# PI-Shield.net
KiCad netlist of a schematic drawn in EAGLE
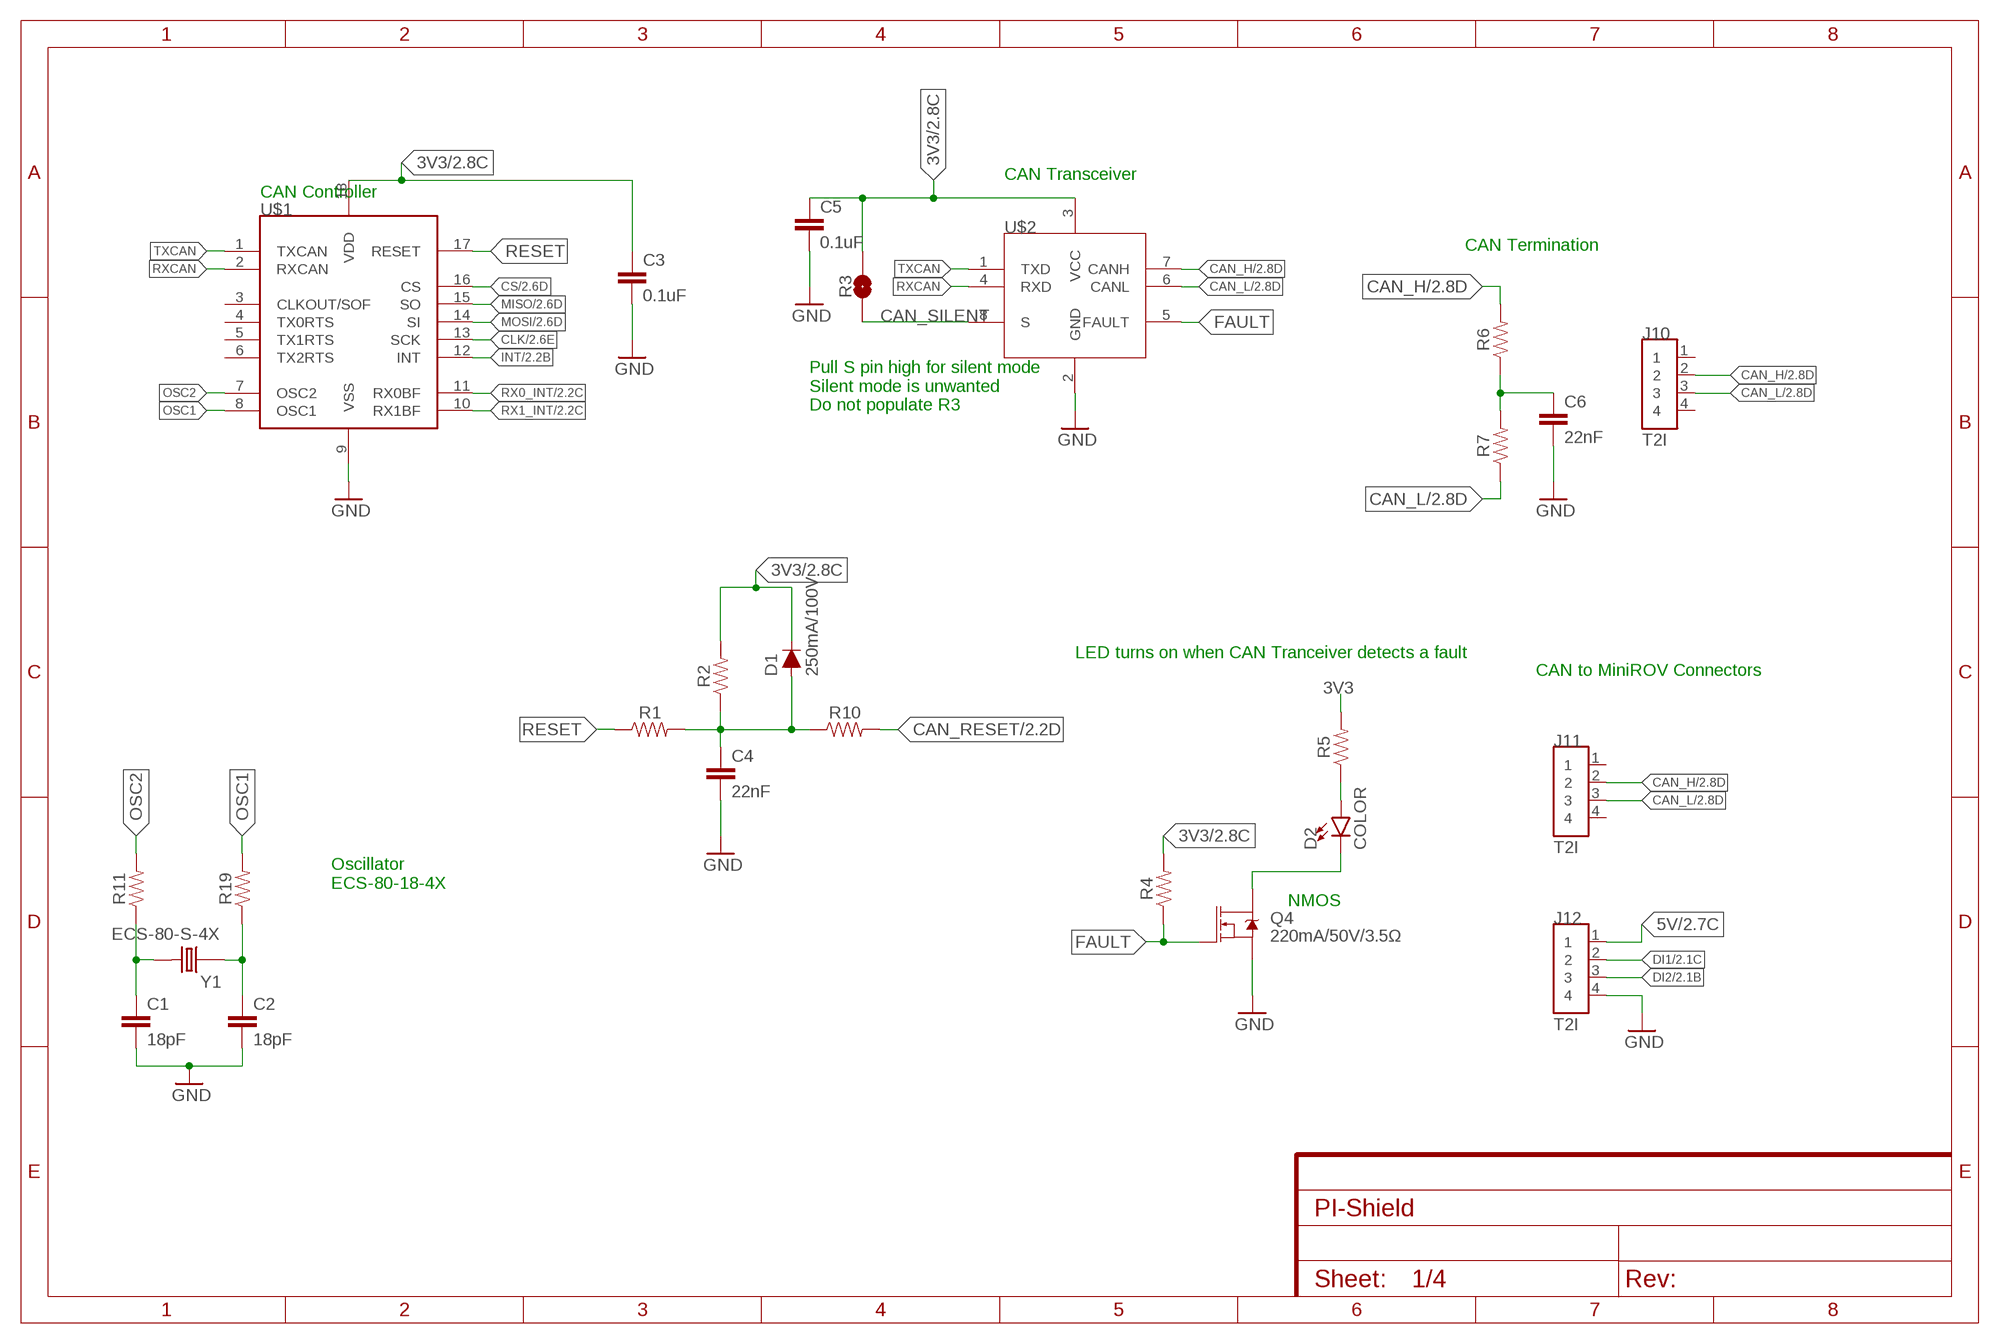
[diagram p0: schematic, sheet 1]
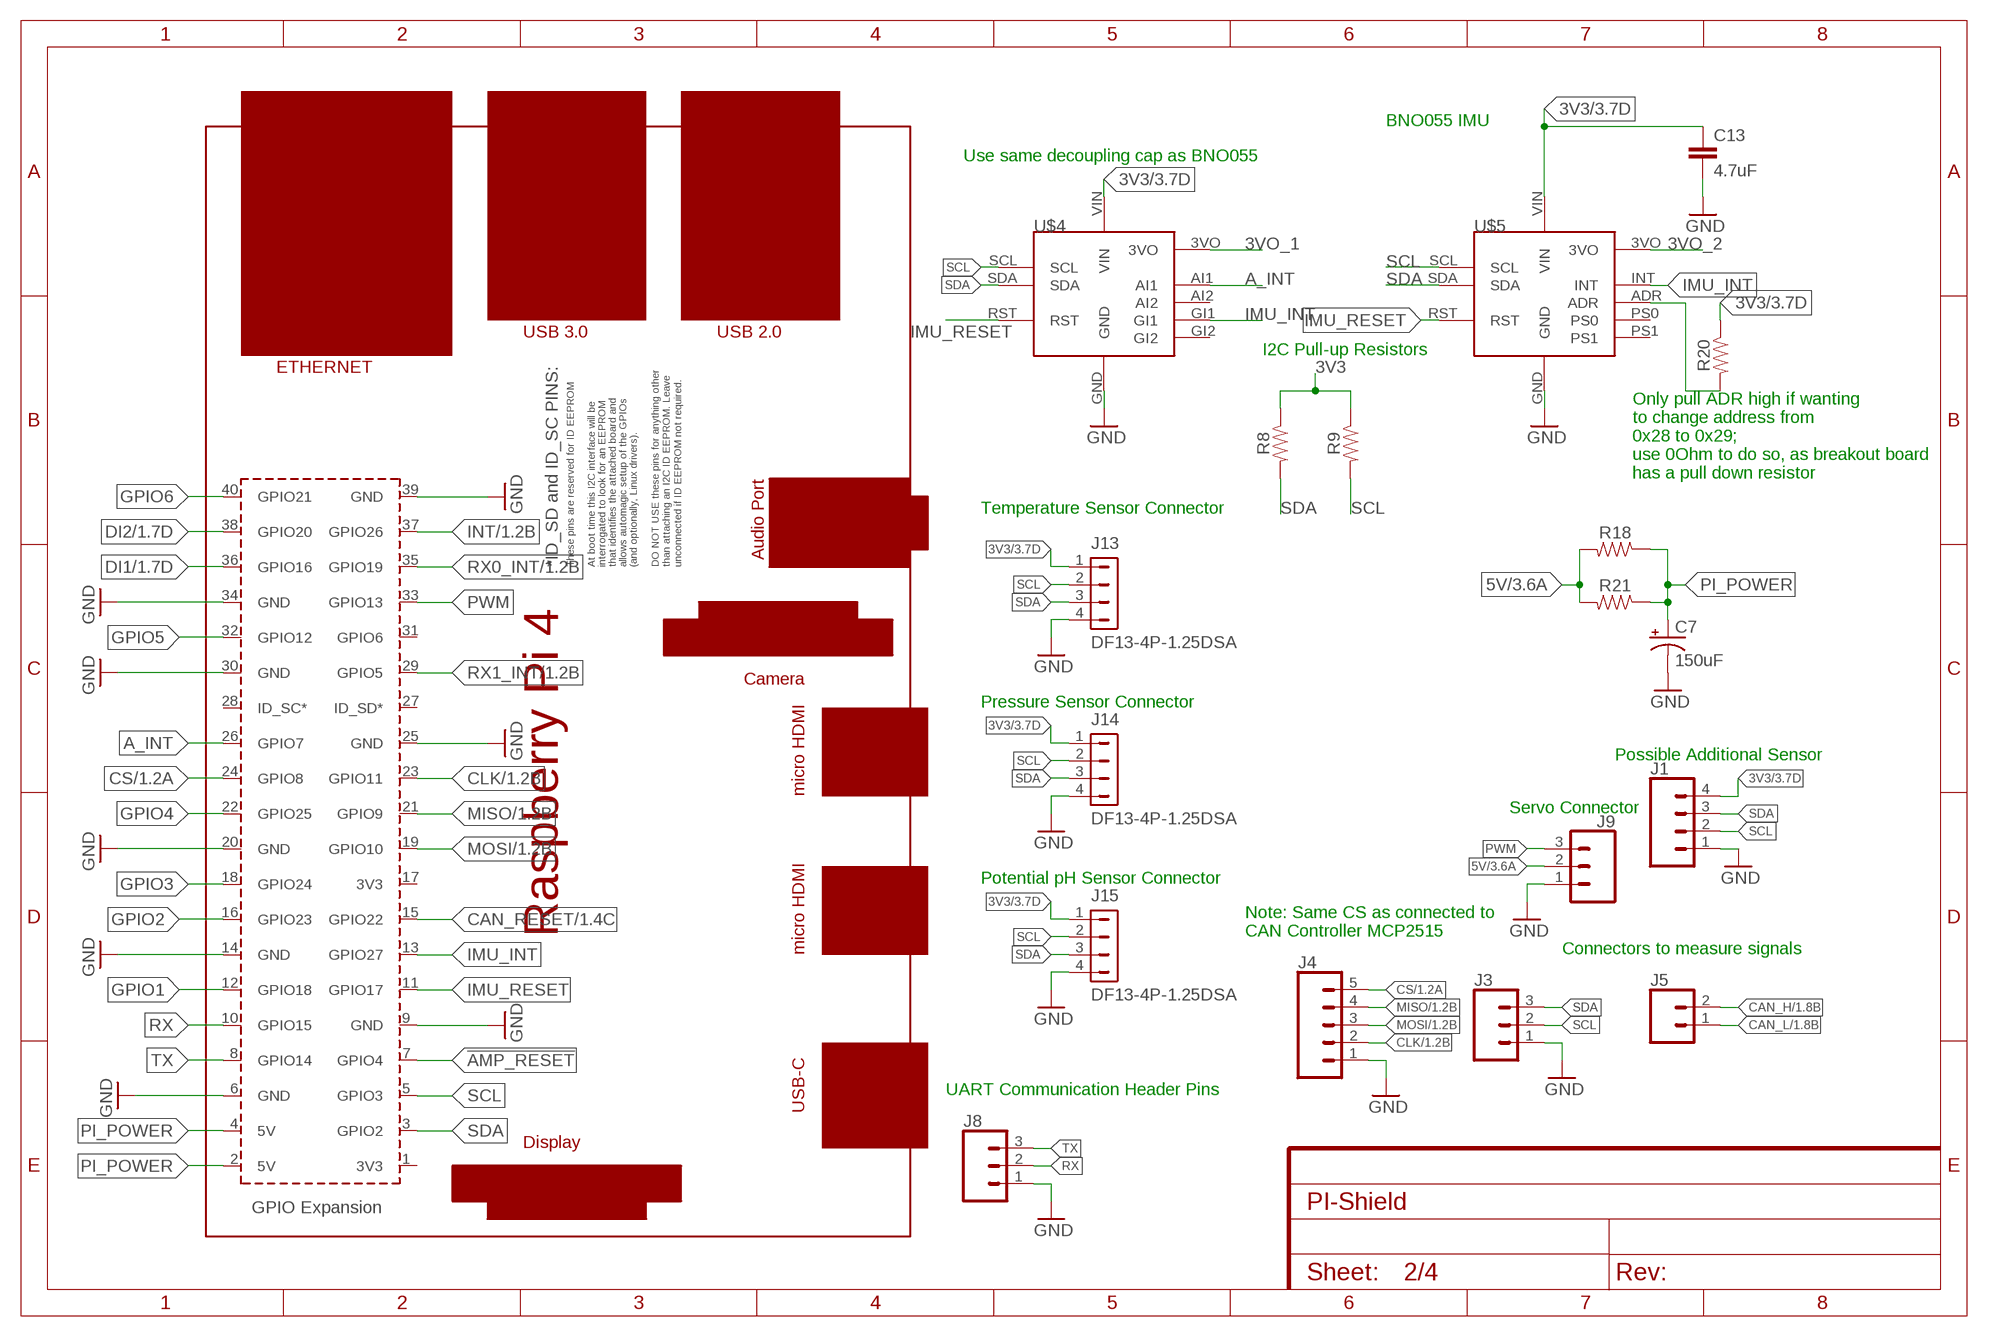
[diagram p1: schematic, sheet 2]
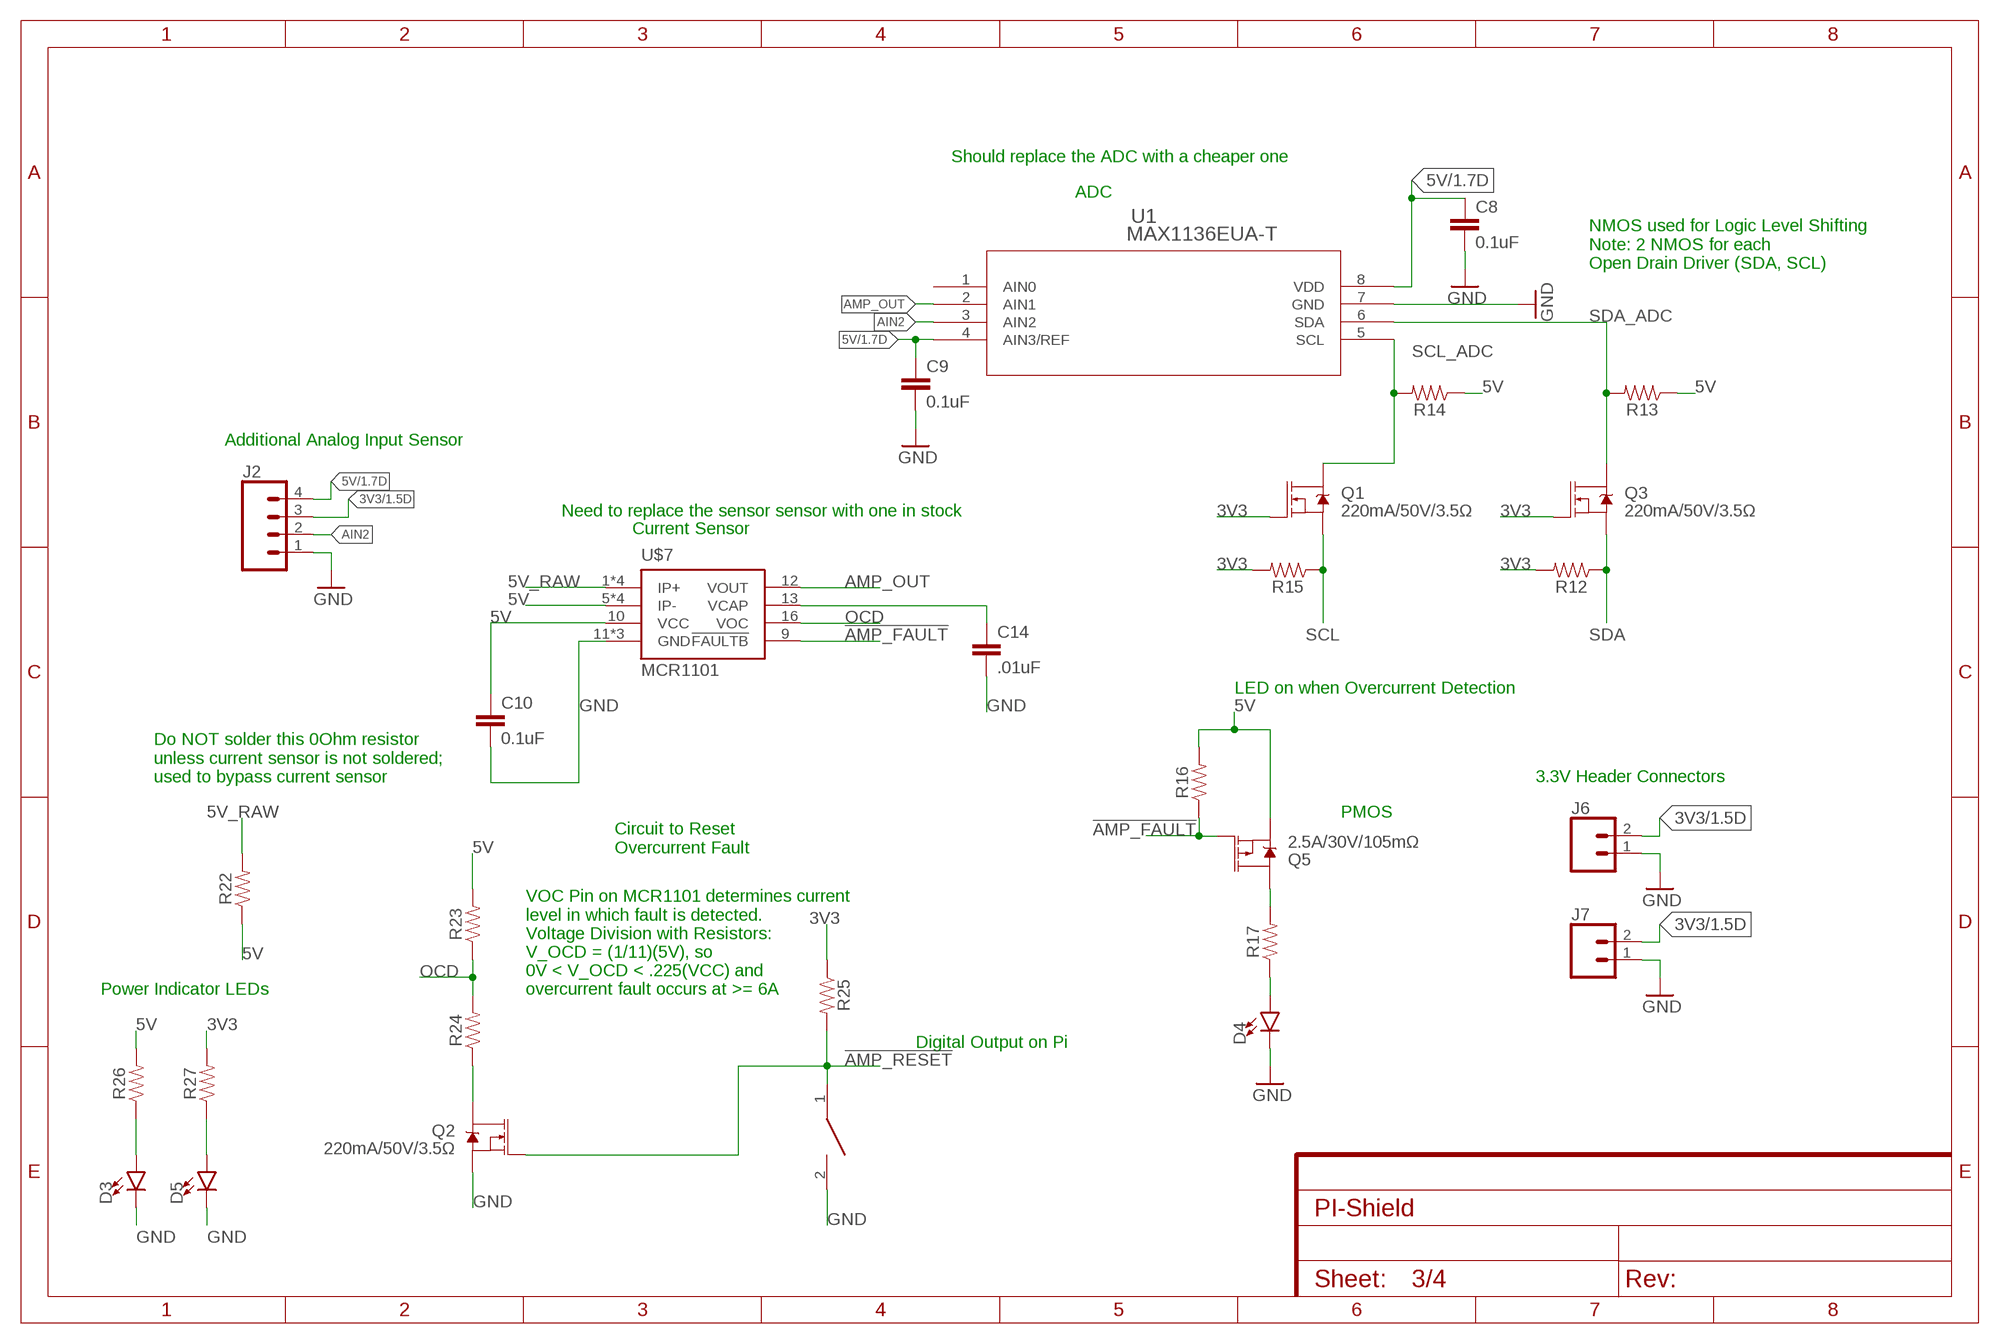
[diagram p2: schematic, sheet 3]
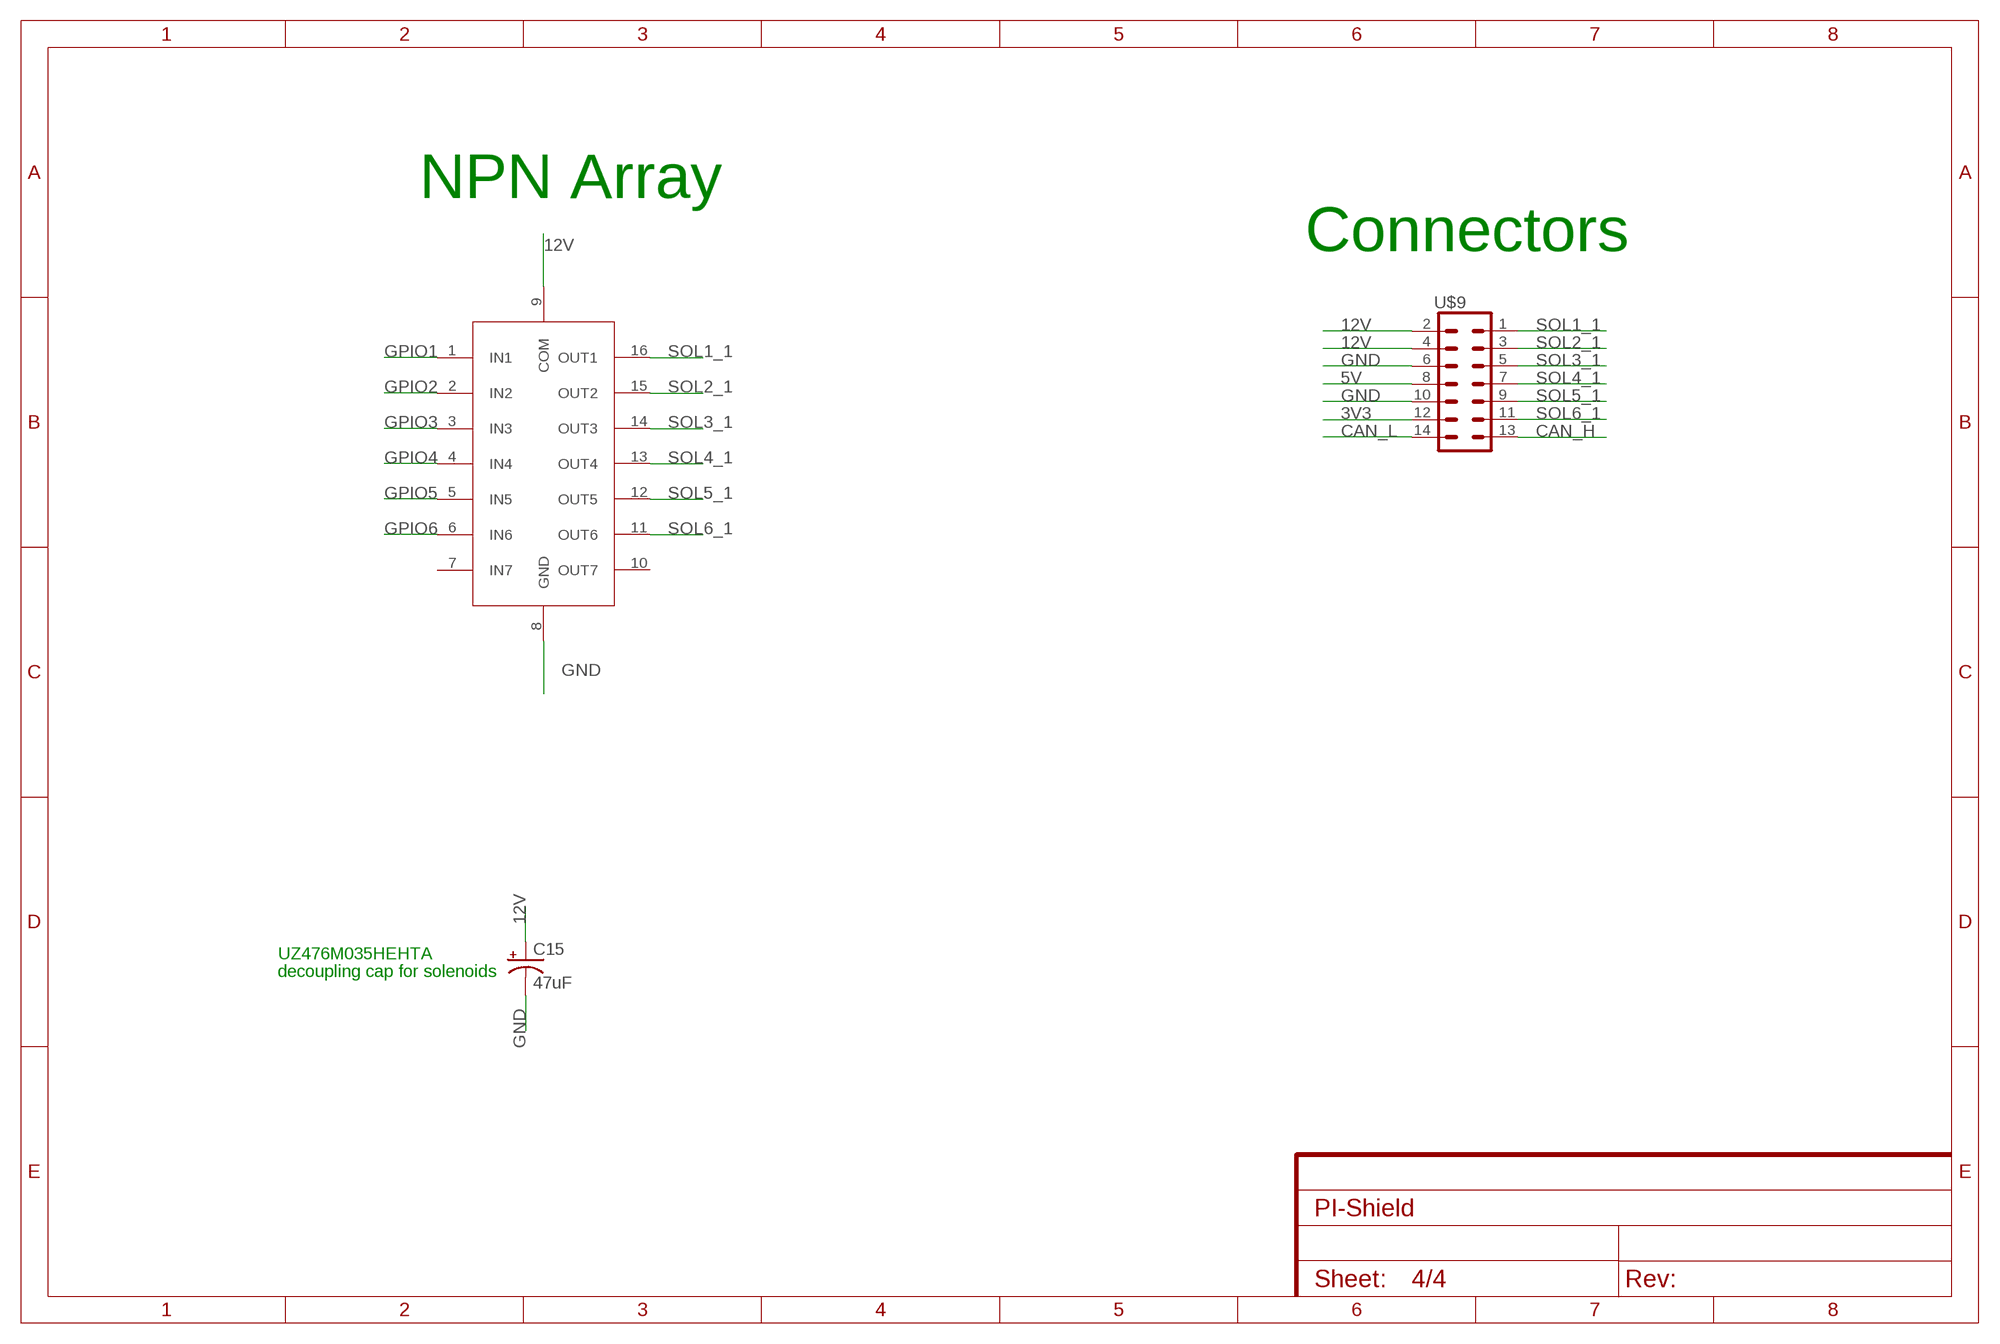
[diagram p3: schematic, sheet 4]

(export (version "E")
  (design (tool "Eeschema 10.0.6"))
  (components
    (comp (ref "C1")
      (value "18pF")
      (footprint "eagle-import:0603")
      (libsource (lib "eagle-import") (part "18PF-0603-50V-5%"))
    )
    (comp (ref "C2")
      (value "18pF")
      (footprint "eagle-import:0603")
      (libsource (lib "eagle-import") (part "18PF-0603-50V-5%"))
    )
    (comp (ref "C3")
      (value "0.1uF")
      (footprint "eagle-import:0603")
      (libsource (lib "eagle-import") (part "22NF/22,000PF-0603-50V-10%"))
    )
    (comp (ref "C4")
      (value "22nF")
      (footprint "eagle-import:0603")
      (libsource (lib "eagle-import") (part "22NF/22,000PF-0603-50V-10%"))
    )
    (comp (ref "C5")
      (value "0.1uF")
      (footprint "eagle-import:0603")
      (libsource (lib "eagle-import") (part "22NF/22,000PF-0603-50V-10%"))
    )
    (comp (ref "C6")
      (value "22nF")
      (footprint "eagle-import:0603")
      (libsource (lib "eagle-import") (part "22NF/22,000PF-0603-50V-10%"))
    )
    (comp (ref "D1")
      (value "250mA/100V")
      (footprint "eagle-import:SOD-323")
      (libsource (lib "eagle-import") (part "DIODE-BAS16J"))
    )
    (comp (ref "D2")
      (value "COLOR")
      (footprint "eagle-import:0805")
      (libsource (lib "eagle-import") (part "LED-0805"))
    )
    (comp (ref "J10")
      (value "T2I")
      (footprint "eagle-import:T2I")
      (libsource (lib "eagle-import") (part "T2I"))
    )
    (comp (ref "J11")
      (value "T2I")
      (footprint "eagle-import:T2I")
      (libsource (lib "eagle-import") (part "T2I"))
    )
    (comp (ref "J12")
      (value "T2I")
      (footprint "eagle-import:T2I")
      (libsource (lib "eagle-import") (part "T2I"))
    )
    (comp (ref "Q4")
      (value "220mA/50V/3.5Ω")
      (footprint "eagle-import:SOT23-3")
      (libsource (lib "eagle-import") (part "MOSFET-NCH-BSS138"))
    )
    (comp (ref "R1")
      (value "RESISTOR0603")
      (footprint "eagle-import:0603")
      (libsource (lib "eagle-import") (part "RESISTOR0603"))
    )
    (comp (ref "R2")
      (value "RESISTOR0603")
      (footprint "eagle-import:0603")
      (libsource (lib "eagle-import") (part "RESISTOR0603"))
    )
    (comp (ref "R3")
      (value "JUMPER-SMT_2_NO_SILK")
      (footprint "eagle-import:SMT-JUMPER_2_NO_SILK")
      (libsource (lib "eagle-import") (part "JUMPER-SMT_2_NO_SILK"))
    )
    (comp (ref "R4")
      (value "RESISTOR0603")
      (footprint "eagle-import:0603")
      (libsource (lib "eagle-import") (part "RESISTOR0603"))
    )
    (comp (ref "R5")
      (value "RESISTOR0603")
      (footprint "eagle-import:0603")
      (libsource (lib "eagle-import") (part "RESISTOR0603"))
    )
    (comp (ref "R6")
      (value "RESISTOR0603")
      (footprint "eagle-import:0603")
      (libsource (lib "eagle-import") (part "RESISTOR0603"))
    )
    (comp (ref "R7")
      (value "RESISTOR0603")
      (footprint "eagle-import:0603")
      (libsource (lib "eagle-import") (part "RESISTOR0603"))
    )
    (comp (ref "R10")
      (value "RESISTOR0603")
      (footprint "eagle-import:0603")
      (libsource (lib "eagle-import") (part "RESISTOR0603"))
    )
    (comp (ref "R11")
      (value "RESISTOR0603")
      (footprint "eagle-import:0603")
      (libsource (lib "eagle-import") (part "RESISTOR0603"))
    )
    (comp (ref "R19")
      (value "RESISTOR0603")
      (footprint "eagle-import:0603")
      (libsource (lib "eagle-import") (part "RESISTOR0603"))
    )
    (comp (ref "U$1")
      (value "MCP2515")
      (footprint "eagle-import:SOIC-18")
      (libsource (lib "eagle-import") (part "MCP2515"))
    )
    (comp (ref "U$2")
      (value "TCAN337D")
      (footprint "eagle-import:SOIC-8")
      (libsource (lib "eagle-import") (part "TCAN337D"))
    )
    (comp (ref "Y1")
      (value "ECS-80-S-4X")
      (footprint "eagle-import:XTAL_ECS-80-S-4X")
      (fields (field (name "DIGI-KEY_PART_NUMBER") "X1057-ND") (field (name "MF") "ECS International"))
      (libsource (lib "eagle-import") (part "ECS-80-S-4X"))
    )
    (comp (ref "C7")
      (value "150uF")
      (footprint "eagle-import:2917(7343-31-METRIC)")
      (libsource (lib "eagle-import") (part "C-TANTALUM(10UF_150UF)"))
    )
    (comp (ref "C13")
      (value "4.7uF")
      (footprint "eagle-import:0603")
      (libsource (lib "eagle-import") (part "22NF/22,000PF-0603-50V-10%"))
    )
    (comp (ref "J1")
      (value "CONN_04")
      (footprint "eagle-import:1X04")
      (libsource (lib "eagle-import") (part "CONN_04"))
    )
    (comp (ref "J3")
      (value "CONN_03")
      (footprint "eagle-import:1X03")
      (libsource (lib "eagle-import") (part "CONN_03"))
    )
    (comp (ref "J4")
      (value "CONN_05")
      (footprint "eagle-import:1X05")
      (libsource (lib "eagle-import") (part "CONN_05"))
    )
    (comp (ref "J5")
      (value "CONN_02")
      (footprint "eagle-import:1X02")
      (libsource (lib "eagle-import") (part "SparkFun-Connectors_513_CONN_02"))
    )
    (comp (ref "J8")
      (value "CONN_03")
      (footprint "eagle-import:1X03")
      (libsource (lib "eagle-import") (part "CONN_03"))
    )
    (comp (ref "J9")
      (value "CONN_03")
      (footprint "eagle-import:1X03")
      (libsource (lib "eagle-import") (part "CONN_03"))
    )
    (comp (ref "J13")
      (value "DF13-4P-1.25DSA")
      (footprint "eagle-import:DF13-4P-1.25DSA")
      (libsource (lib "eagle-import") (part "DF13-4P-1.25DSA"))
    )
    (comp (ref "J14")
      (value "DF13-4P-1.25DSA")
      (footprint "eagle-import:DF13-4P-1.25DSA")
      (libsource (lib "eagle-import") (part "DF13-4P-1.25DSA"))
    )
    (comp (ref "J15")
      (value "DF13-4P-1.25DSA")
      (footprint "eagle-import:DF13-4P-1.25DSA")
      (libsource (lib "eagle-import") (part "DF13-4P-1.25DSA"))
    )
    (comp (ref "R8")
      (value "RESISTOR0603")
      (footprint "eagle-import:0603")
      (libsource (lib "eagle-import") (part "RESISTOR0603"))
    )
    (comp (ref "R9")
      (value "RESISTOR0603")
      (footprint "eagle-import:0603")
      (libsource (lib "eagle-import") (part "RESISTOR0603"))
    )
    (comp (ref "R18")
      (value "RESISTOR0603")
      (footprint "eagle-import:0603")
      (libsource (lib "eagle-import") (part "RESISTOR0603"))
    )
    (comp (ref "R20")
      (value "RESISTOR0603")
      (footprint "eagle-import:0603")
      (libsource (lib "eagle-import") (part "RESISTOR0603"))
    )
    (comp (ref "R21")
      (value "RESISTOR0603")
      (footprint "eagle-import:0603")
      (libsource (lib "eagle-import") (part "RESISTOR0603"))
    )
    (comp (ref "U$4")
      (value "ADAFRUIT-FXOS8700-FXAS21002")
      (footprint "eagle-import:ADAFRUIT-FXOS8700-FXAS21002")
      (libsource (lib "eagle-import") (part "ADAFRUIT-FXOS8700-FXAS21002"))
    )
    (comp (ref "U$5")
      (value "ADAFRUIT-BNO055")
      (footprint "eagle-import:ADAFRUIT-BNO055")
      (libsource (lib "eagle-import") (part "ADAFRUIT-BNO055"))
    )
    (comp (ref "U$8")
      (value "RPI4")
      (footprint "eagle-import:RPI4")
      (libsource (lib "eagle-import") (part "RPI4"))
    )
    (comp (ref "C8")
      (value "0.1uF")
      (footprint "eagle-import:0603")
      (libsource (lib "eagle-import") (part "22NF/22,000PF-0603-50V-10%"))
    )
    (comp (ref "C9")
      (value "0.1uF")
      (footprint "eagle-import:0603")
      (libsource (lib "eagle-import") (part "22NF/22,000PF-0603-50V-10%"))
    )
    (comp (ref "C10")
      (value "0.1uF")
      (footprint "eagle-import:0603")
      (libsource (lib "eagle-import") (part "22NF/22,000PF-0603-50V-10%"))
    )
    (comp (ref "C14")
      (value ".01uF")
      (footprint "eagle-import:0603")
      (libsource (lib "eagle-import") (part "22NF/22,000PF-0603-50V-10%"))
    )
    (comp (ref "D3")
      (value "LED0603")
      (footprint "eagle-import:LED-0603")
      (libsource (lib "eagle-import") (part "LED0603"))
    )
    (comp (ref "D4")
      (value "LED0603")
      (footprint "eagle-import:LED-0603")
      (libsource (lib "eagle-import") (part "LED0603"))
    )
    (comp (ref "D5")
      (value "LED0603")
      (footprint "eagle-import:LED-0603")
      (libsource (lib "eagle-import") (part "LED0603"))
    )
    (comp (ref "J2")
      (value "CONN_04")
      (footprint "eagle-import:1X04")
      (libsource (lib "eagle-import") (part "CONN_04"))
    )
    (comp (ref "J6")
      (value "CONN_02")
      (footprint "eagle-import:1X02")
      (libsource (lib "eagle-import") (part "CONN_02"))
    )
    (comp (ref "J7")
      (value "CONN_02")
      (footprint "eagle-import:1X02")
      (libsource (lib "eagle-import") (part "CONN_02"))
    )
    (comp (ref "Q1")
      (value "220mA/50V/3.5Ω")
      (footprint "eagle-import:SOT23-3")
      (libsource (lib "eagle-import") (part "MOSFET-NCH-BSS138"))
    )
    (comp (ref "Q2")
      (value "220mA/50V/3.5Ω")
      (footprint "eagle-import:SOT23-3")
      (libsource (lib "eagle-import") (part "MOSFET-NCH-BSS138"))
    )
    (comp (ref "Q3")
      (value "220mA/50V/3.5Ω")
      (footprint "eagle-import:SOT23-3")
      (libsource (lib "eagle-import") (part "MOSFET-NCH-BSS138"))
    )
    (comp (ref "Q5")
      (value "2.5A/30V/105mΩ")
      (footprint "eagle-import:SOT23-3")
      (libsource (lib "eagle-import") (part "MOSFET_PCH-DMG2307L"))
    )
    (comp (ref "R12")
      (value "RESISTOR0603")
      (footprint "eagle-import:0603")
      (libsource (lib "eagle-import") (part "RESISTOR0603"))
    )
    (comp (ref "R13")
      (value "RESISTOR0603")
      (footprint "eagle-import:0603")
      (libsource (lib "eagle-import") (part "RESISTOR0603"))
    )
    (comp (ref "R14")
      (value "RESISTOR0603")
      (footprint "eagle-import:0603")
      (libsource (lib "eagle-import") (part "RESISTOR0603"))
    )
    (comp (ref "R15")
      (value "RESISTOR0603")
      (footprint "eagle-import:0603")
      (libsource (lib "eagle-import") (part "RESISTOR0603"))
    )
    (comp (ref "R16")
      (value "RESISTOR0603")
      (footprint "eagle-import:0603")
      (libsource (lib "eagle-import") (part "RESISTOR0603"))
    )
    (comp (ref "R17")
      (value "RESISTOR0603")
      (footprint "eagle-import:0603")
      (libsource (lib "eagle-import") (part "RESISTOR0603"))
    )
    (comp (ref "R22")
      (value "RESISTOR0603")
      (footprint "eagle-import:0603")
      (libsource (lib "eagle-import") (part "RESISTOR0603"))
    )
    (comp (ref "R23")
      (value "RESISTOR0603")
      (footprint "eagle-import:0603")
      (libsource (lib "eagle-import") (part "RESISTOR0603"))
    )
    (comp (ref "R24")
      (value "RESISTOR0603")
      (footprint "eagle-import:0603")
      (libsource (lib "eagle-import") (part "RESISTOR0603"))
    )
    (comp (ref "R25")
      (value "RESISTOR0603")
      (footprint "eagle-import:0603")
      (libsource (lib "eagle-import") (part "RESISTOR0603"))
    )
    (comp (ref "R26")
      (value "RESISTOR0603")
      (footprint "eagle-import:0603")
      (libsource (lib "eagle-import") (part "RESISTOR0603"))
    )
    (comp (ref "R27")
      (value "RESISTOR0603")
      (footprint "eagle-import:0603")
      (libsource (lib "eagle-import") (part "RESISTOR0603"))
    )
    (comp (ref "U$6")
      (value "DISCRETECOMPONENTS_SWITCH")
      (footprint "eagle-import:DISCRETECOMPONENTS_SW_2512")
      (libsource (lib "eagle-import") (part "DISCRETECOMPONENTS_SWITCH"))
    )
    (comp (ref "U$7")
      (value "MCR1101")
      (footprint "eagle-import:SOIC-16")
      (libsource (lib "eagle-import") (part "MCR1101"))
    )
    (comp (ref "U1")
      (value "MAX1136EUA-T")
      (footprint "eagle-import:21-0036K")
      (fields
        (field (name "DIGI-KEY_PART_NUMBER") "MAX1136EUA+-ND")
        (field (name "MF") "Maxim Integrated")
        (field (name "MP") "MAX1136EUA+")
      )
      (libsource (lib "eagle-import") (part "MAX1136EUA-T"))
    )
    (comp (ref "C15")
      (value "47uF")
      (footprint "eagle-import:PANASONIC_D")
      (libsource (lib "eagle-import") (part "47UF-POLAR-PANASONIC_D-35V-20%"))
    )
    (comp (ref "U$9")
      (value "7X_CONN")
      (footprint "eagle-import:IPL7X2")
      (libsource (lib "eagle-import") (part "7X_CONN"))
    )
    (comp (ref "U3")
      (value "ULN2003V12")
      (footprint "eagle-import:ULN2003V12")
      (fields (field (name "MANUFACTURER") "Diodes Inc."))
      (libsource (lib "eagle-import") (part "ULN2003V12"))
    )
  )
  (nets
    (net (code "1") (name "3V3") (class "Default")
      (node (ref "C13") (pin "1") (pinfunction "1_1") (pintype "passive"))
      (node (ref "C3") (pin "1") (pinfunction "1_1") (pintype "passive"))
      (node (ref "C5") (pin "1") (pinfunction "1_1") (pintype "passive"))
      (node (ref "D1") (pin "C") (pinfunction "C_C") (pintype "passive"))
      (node (ref "J1") (pin "4") (pinfunction "4_4") (pintype "passive"))
      (node (ref "J13") (pin "1") (pinfunction "1_1") (pintype "passive"))
      (node (ref "J14") (pin "1") (pinfunction "1_1") (pintype "passive"))
      (node (ref "J15") (pin "1") (pinfunction "1_1") (pintype "passive"))
      (node (ref "J2") (pin "3") (pinfunction "3_3") (pintype "passive"))
      (node (ref "J6") (pin "2") (pinfunction "2_2") (pintype "passive"))
      (node (ref "J7") (pin "2") (pinfunction "2_2") (pintype "passive"))
      (node (ref "Q1") (pin "1") (pinfunction "G_1") (pintype "bidirectional"))
      (node (ref "Q3") (pin "1") (pinfunction "G_1") (pintype "bidirectional"))
      (node (ref "R12") (pin "2") (pinfunction "2_2") (pintype "passive"))
      (node (ref "R15") (pin "2") (pinfunction "2_2") (pintype "passive"))
      (node (ref "R2") (pin "2") (pinfunction "2_2") (pintype "passive"))
      (node (ref "R20") (pin "1") (pinfunction "1_1") (pintype "passive"))
      (node (ref "R25") (pin "1") (pinfunction "1_1") (pintype "passive"))
      (node (ref "R27") (pin "2") (pinfunction "2_2") (pintype "passive"))
      (node (ref "R3") (pin "2") (pinfunction "2_2") (pintype "passive"))
      (node (ref "R4") (pin "2") (pinfunction "2_2") (pintype "passive"))
      (node (ref "R5") (pin "2") (pinfunction "2_2") (pintype "passive"))
      (node (ref "R8") (pin "1") (pinfunction "1_1") (pintype "passive"))
      (node (ref "R9") (pin "1") (pinfunction "1_1") (pintype "passive"))
      (node (ref "U$1") (pin "18") (pinfunction "VDD_18") (pintype "bidirectional"))
      (node (ref "U$2") (pin "3") (pinfunction "VCC_3") (pintype "bidirectional"))
      (node (ref "U$4") (pin "VIN") (pinfunction "VIN_VIN") (pintype "power_in"))
      (node (ref "U$5") (pin "VIN") (pinfunction "VIN_VIN") (pintype "power_in"))
      (node (ref "U$9") (pin "12") (pinfunction "23_12") (pintype "passive"))
    )
    (net (code "2") (name "3VO_1") (class "Default")
      (node (ref "U$4") (pin "3VO") (pinfunction "3VO_3VO") (pintype "power_in"))
    )
    (net (code "3") (name "3VO_2") (class "Default")
      (node (ref "U$5") (pin "3VO") (pinfunction "3VO_3VO") (pintype "power_in"))
    )
    (net (code "4") (name "5V") (class "Default")
      (node (ref "C10") (pin "1") (pinfunction "1_1") (pintype "passive"))
      (node (ref "C8") (pin "1") (pinfunction "1_1") (pintype "passive"))
      (node (ref "C9") (pin "1") (pinfunction "1_1") (pintype "passive"))
      (node (ref "J12") (pin "1") (pinfunction "1_1") (pintype "bidirectional"))
      (node (ref "J2") (pin "4") (pinfunction "4_4") (pintype "passive"))
      (node (ref "J9") (pin "2") (pinfunction "2_2") (pintype "passive"))
      (node (ref "Q5") (pin "2") (pinfunction "S_2") (pintype "bidirectional"))
      (node (ref "R13") (pin "1") (pinfunction "1_1") (pintype "passive"))
      (node (ref "R14") (pin "1") (pinfunction "1_1") (pintype "passive"))
      (node (ref "R16") (pin "2") (pinfunction "2_2") (pintype "passive"))
      (node (ref "R18") (pin "2") (pinfunction "2_2") (pintype "passive"))
      (node (ref "R21") (pin "2") (pinfunction "2_2") (pintype "passive"))
      (node (ref "R22") (pin "1") (pinfunction "1_1") (pintype "passive"))
      (node (ref "R23") (pin "2") (pinfunction "2_2") (pintype "passive"))
      (node (ref "R26") (pin "2") (pinfunction "2_2") (pintype "passive"))
      (node (ref "U$7") (pin "10") (pinfunction "VCC_10") (pintype "bidirectional"))
      (node (ref "U$7") (pin "5") (pinfunction "IP-_5") (pintype "bidirectional"))
      (node (ref "U$7") (pin "6") (pinfunction "IP-_6") (pintype "bidirectional"))
      (node (ref "U$7") (pin "7") (pinfunction "IP-_7") (pintype "bidirectional"))
      (node (ref "U$7") (pin "8") (pinfunction "IP-_8") (pintype "bidirectional"))
      (node (ref "U$9") (pin "8") (pinfunction "19_8") (pintype "passive"))
      (node (ref "U1") (pin "4") (pinfunction "AIN3/REF_4") (pintype "bidirectional"))
      (node (ref "U1") (pin "8") (pinfunction "VDD_8") (pintype "power_in"))
    )
    (net (code "5") (name "5V_RAW") (class "Default")
      (node (ref "R22") (pin "2") (pinfunction "2_2") (pintype "passive"))
      (node (ref "U$7") (pin "1") (pinfunction "IP+_1") (pintype "bidirectional"))
      (node (ref "U$7") (pin "2") (pinfunction "IP+_2") (pintype "bidirectional"))
      (node (ref "U$7") (pin "3") (pinfunction "IP+_3") (pintype "bidirectional"))
      (node (ref "U$7") (pin "4") (pinfunction "IP+_4") (pintype "bidirectional"))
    )
    (net (code "6") (name "12V") (class "Default")
      (node (ref "C15") (pin "+") (pinfunction "+_+") (pintype "passive"))
      (node (ref "U$9") (pin "2") (pinfunction "13_2") (pintype "passive"))
      (node (ref "U$9") (pin "4") (pinfunction "15_4") (pintype "passive"))
      (node (ref "U3") (pin "9") (pinfunction "COM_9") (pintype "bidirectional"))
    )
    (net (code "7") (name "AIN2") (class "Default")
      (node (ref "J2") (pin "2") (pinfunction "2_2") (pintype "passive"))
      (node (ref "U1") (pin "3") (pinfunction "AIN2_3") (pintype "bidirectional"))
    )
    (net (code "8") (name "AMP_OUT") (class "Default")
      (node (ref "U$7") (pin "12") (pinfunction "VOUT_12") (pintype "bidirectional"))
      (node (ref "U1") (pin "2") (pinfunction "AIN1_2") (pintype "bidirectional"))
    )
    (net (code "9") (name "A_INT") (class "Default")
      (node (ref "U$4") (pin "AI1") (pinfunction "AI1_AI1") (pintype "output"))
      (node (ref "U$8") (pin "26") (pinfunction "GPIO7_26") (pintype "bidirectional"))
    )
    (net (code "10") (name "CAN_H") (class "Default")
      (node (ref "J10") (pin "2") (pinfunction "2_2") (pintype "bidirectional"))
      (node (ref "J11") (pin "2") (pinfunction "2_2") (pintype "bidirectional"))
      (node (ref "J5") (pin "2") (pinfunction "2_2") (pintype "passive"))
      (node (ref "R6") (pin "2") (pinfunction "2_2") (pintype "passive"))
      (node (ref "U$2") (pin "7") (pinfunction "CANH_7") (pintype "bidirectional"))
      (node (ref "U$9") (pin "13") (pinfunction "1_13") (pintype "passive"))
    )
    (net (code "11") (name "CAN_L") (class "Default")
      (node (ref "J10") (pin "3") (pinfunction "3_3") (pintype "bidirectional"))
      (node (ref "J11") (pin "3") (pinfunction "3_3") (pintype "bidirectional"))
      (node (ref "J5") (pin "1") (pinfunction "1_1") (pintype "passive"))
      (node (ref "R7") (pin "1") (pinfunction "1_1") (pintype "passive"))
      (node (ref "U$2") (pin "6") (pinfunction "CANL_6") (pintype "bidirectional"))
      (node (ref "U$9") (pin "14") (pinfunction "2_14") (pintype "passive"))
    )
    (net (code "12") (name "CAN_RESET") (class "Default")
      (node (ref "R10") (pin "2") (pinfunction "2_2") (pintype "passive"))
      (node (ref "U$8") (pin "15") (pinfunction "GPIO22_15") (pintype "bidirectional"))
    )
    (net (code "13") (name "CAN_SILENT") (class "Default")
      (node (ref "R3") (pin "1") (pinfunction "1_1") (pintype "passive"))
      (node (ref "U$2") (pin "8") (pinfunction "S_8") (pintype "bidirectional"))
    )
    (net (code "14") (name "CLK") (class "Default")
      (node (ref "J4") (pin "2") (pinfunction "2_2") (pintype "passive"))
      (node (ref "U$1") (pin "13") (pinfunction "SCK_13") (pintype "bidirectional"))
      (node (ref "U$8") (pin "23") (pinfunction "GPIO11_23") (pintype "bidirectional"))
    )
    (net (code "15") (name "CS") (class "Default")
      (node (ref "J4") (pin "5") (pinfunction "5_5") (pintype "passive"))
      (node (ref "U$1") (pin "16") (pinfunction "CS_16") (pintype "bidirectional"))
      (node (ref "U$8") (pin "24") (pinfunction "GPIO8_24") (pintype "bidirectional"))
    )
    (net (code "16") (name "DI1") (class "Default")
      (node (ref "J12") (pin "2") (pinfunction "2_2") (pintype "bidirectional"))
      (node (ref "U$8") (pin "36") (pinfunction "GPIO16_36") (pintype "bidirectional"))
    )
    (net (code "17") (name "DI2") (class "Default")
      (node (ref "J12") (pin "3") (pinfunction "3_3") (pintype "bidirectional"))
      (node (ref "U$8") (pin "38") (pinfunction "GPIO20_38") (pintype "bidirectional"))
    )
    (net (code "18") (name "FAULT") (class "Default")
      (node (ref "Q4") (pin "1") (pinfunction "G_1") (pintype "bidirectional"))
      (node (ref "R4") (pin "1") (pinfunction "1_1") (pintype "passive"))
      (node (ref "U$2") (pin "5") (pinfunction "FAULT_5") (pintype "bidirectional"))
    )
    (net (code "19") (name "GND") (class "Default")
      (node (ref "C1") (pin "2") (pinfunction "2_2") (pintype "passive"))
      (node (ref "C10") (pin "2") (pinfunction "2_2") (pintype "passive"))
      (node (ref "C13") (pin "2") (pinfunction "2_2") (pintype "passive"))
      (node (ref "C14") (pin "2") (pinfunction "2_2") (pintype "passive"))
      (node (ref "C15") (pin "-") (pinfunction "-_-") (pintype "passive"))
      (node (ref "C2") (pin "2") (pinfunction "2_2") (pintype "passive"))
      (node (ref "C3") (pin "2") (pinfunction "2_2") (pintype "passive"))
      (node (ref "C4") (pin "2") (pinfunction "2_2") (pintype "passive"))
      (node (ref "C5") (pin "2") (pinfunction "2_2") (pintype "passive"))
      (node (ref "C6") (pin "2") (pinfunction "2_2") (pintype "passive"))
      (node (ref "C7") (pin "-") (pinfunction "-_-") (pintype "passive"))
      (node (ref "C8") (pin "2") (pinfunction "2_2") (pintype "passive"))
      (node (ref "C9") (pin "2") (pinfunction "2_2") (pintype "passive"))
      (node (ref "D3") (pin "C") (pinfunction "C_C") (pintype "passive"))
      (node (ref "D4") (pin "C") (pinfunction "C_C") (pintype "passive"))
      (node (ref "D5") (pin "C") (pinfunction "C_C") (pintype "passive"))
      (node (ref "J1") (pin "1") (pinfunction "1_1") (pintype "passive"))
      (node (ref "J12") (pin "4") (pinfunction "4_4") (pintype "bidirectional"))
      (node (ref "J13") (pin "4") (pinfunction "4_4") (pintype "passive"))
      (node (ref "J14") (pin "4") (pinfunction "4_4") (pintype "passive"))
      (node (ref "J15") (pin "4") (pinfunction "4_4") (pintype "passive"))
      (node (ref "J2") (pin "1") (pinfunction "1_1") (pintype "passive"))
      (node (ref "J3") (pin "1") (pinfunction "1_1") (pintype "passive"))
      (node (ref "J4") (pin "1") (pinfunction "1_1") (pintype "passive"))
      (node (ref "J6") (pin "1") (pinfunction "1_1") (pintype "passive"))
      (node (ref "J7") (pin "1") (pinfunction "1_1") (pintype "passive"))
      (node (ref "J8") (pin "1") (pinfunction "1_1") (pintype "passive"))
      (node (ref "J9") (pin "1") (pinfunction "1_1") (pintype "passive"))
      (node (ref "Q2") (pin "2") (pinfunction "S_2") (pintype "bidirectional"))
      (node (ref "Q4") (pin "2") (pinfunction "S_2") (pintype "bidirectional"))
      (node (ref "U$1") (pin "9") (pinfunction "VSS_9") (pintype "bidirectional"))
      (node (ref "U$2") (pin "2") (pinfunction "GND_2") (pintype "bidirectional"))
      (node (ref "U$4") (pin "GND") (pinfunction "GND_GND") (pintype "power_in"))
      (node (ref "U$5") (pin "GND") (pinfunction "GND_GND") (pintype "power_in"))
      (node (ref "U$6") (pin "2") (pinfunction "P$2_2") (pintype "bidirectional"))
      (node (ref "U$7") (pin "11") (pinfunction "GND_11") (pintype "bidirectional"))
      (node (ref "U$7") (pin "14") (pinfunction "GND_14") (pintype "bidirectional"))
      (node (ref "U$7") (pin "15") (pinfunction "GND_15") (pintype "bidirectional"))
      (node (ref "U$8") (pin "14") (pinfunction "GND_14") (pintype "bidirectional"))
      (node (ref "U$8") (pin "20") (pinfunction "GND_20") (pintype "bidirectional"))
      (node (ref "U$8") (pin "25") (pinfunction "GND_25") (pintype "bidirectional"))
      (node (ref "U$8") (pin "30") (pinfunction "GND_30") (pintype "bidirectional"))
      (node (ref "U$8") (pin "34") (pinfunction "GND_34") (pintype "bidirectional"))
      (node (ref "U$8") (pin "39") (pinfunction "GND_39") (pintype "bidirectional"))
      (node (ref "U$8") (pin "6") (pinfunction "GND_6") (pintype "bidirectional"))
      (node (ref "U$8") (pin "9") (pinfunction "GND_9") (pintype "bidirectional"))
      (node (ref "U$9") (pin "10") (pinfunction "21_10") (pintype "passive"))
      (node (ref "U$9") (pin "6") (pinfunction "17_6") (pintype "passive"))
      (node (ref "U1") (pin "7") (pinfunction "GND_7") (pintype "power_in"))
      (node (ref "U3") (pin "8") (pinfunction "GND_8") (pintype "bidirectional"))
    )
    (net (code "20") (name "GPIO1") (class "Default")
      (node (ref "U$8") (pin "12") (pinfunction "GPIO18_12") (pintype "bidirectional"))
      (node (ref "U3") (pin "1") (pinfunction "IN1_1") (pintype "bidirectional"))
    )
    (net (code "21") (name "GPIO2") (class "Default")
      (node (ref "U$8") (pin "16") (pinfunction "GPIO23_16") (pintype "bidirectional"))
      (node (ref "U3") (pin "2") (pinfunction "IN2_2") (pintype "bidirectional"))
    )
    (net (code "22") (name "GPIO3") (class "Default")
      (node (ref "U$8") (pin "18") (pinfunction "GPIO24_18") (pintype "bidirectional"))
      (node (ref "U3") (pin "3") (pinfunction "IN3_3") (pintype "bidirectional"))
    )
    (net (code "23") (name "GPIO4") (class "Default")
      (node (ref "U$8") (pin "22") (pinfunction "GPIO25_22") (pintype "bidirectional"))
      (node (ref "U3") (pin "4") (pinfunction "IN4_4") (pintype "bidirectional"))
    )
    (net (code "24") (name "GPIO5") (class "Default")
      (node (ref "U$8") (pin "32") (pinfunction "GPIO12_32") (pintype "bidirectional"))
      (node (ref "U3") (pin "5") (pinfunction "IN5_5") (pintype "bidirectional"))
    )
    (net (code "25") (name "GPIO6") (class "Default")
      (node (ref "U$8") (pin "40") (pinfunction "GPIO21_40") (pintype "bidirectional"))
      (node (ref "U3") (pin "6") (pinfunction "IN6_6") (pintype "bidirectional"))
    )
    (net (code "26") (name "IMU_INT") (class "Default")
      (node (ref "U$4") (pin "GI1") (pinfunction "GI1_GI1") (pintype "output"))
      (node (ref "U$5") (pin "INT") (pinfunction "INT_INT") (pintype "output"))
      (node (ref "U$8") (pin "13") (pinfunction "GPIO27_13") (pintype "bidirectional"))
    )
    (net (code "27") (name "IMU_RESET") (class "Default")
      (node (ref "U$4") (pin "RST") (pinfunction "RST_RST") (pintype "input"))
      (node (ref "U$5") (pin "RST") (pinfunction "RST_RST") (pintype "input"))
      (node (ref "U$8") (pin "11") (pinfunction "GPIO17_11") (pintype "bidirectional"))
    )
    (net (code "28") (name "INT") (class "Default")
      (node (ref "U$1") (pin "12") (pinfunction "INT_12") (pintype "bidirectional"))
      (node (ref "U$8") (pin "37") (pinfunction "GPIO26_37") (pintype "bidirectional"))
    )
    (net (code "29") (name "MISO") (class "Default")
      (node (ref "J4") (pin "4") (pinfunction "4_4") (pintype "passive"))
      (node (ref "U$1") (pin "15") (pinfunction "SO_15") (pintype "bidirectional"))
      (node (ref "U$8") (pin "21") (pinfunction "GPIO9_21") (pintype "bidirectional"))
    )
    (net (code "30") (name "MOSI") (class "Default")
      (node (ref "J4") (pin "3") (pinfunction "3_3") (pintype "passive"))
      (node (ref "U$1") (pin "14") (pinfunction "SI_14") (pintype "bidirectional"))
      (node (ref "U$8") (pin "19") (pinfunction "GPIO10_19") (pintype "bidirectional"))
    )
    (net (code "31") (name "Net-(C1-Pad1)") (class "Default")
      (node (ref "C1") (pin "1") (pinfunction "1_1") (pintype "passive"))
      (node (ref "R11") (pin "1") (pinfunction "1_1") (pintype "passive"))
      (node (ref "Y1") (pin "2") (pinfunction "2_2") (pintype "passive"))
    )
    (net (code "32") (name "Net-(C2-Pad1)") (class "Default")
      (node (ref "C2") (pin "1") (pinfunction "1_1") (pintype "passive"))
      (node (ref "R19") (pin "1") (pinfunction "1_1") (pintype "passive"))
      (node (ref "Y1") (pin "1") (pinfunction "1_1") (pintype "passive"))
    )
    (net (code "33") (name "Net-(C4-Pad1)") (class "Default")
      (node (ref "C4") (pin "1") (pinfunction "1_1") (pintype "passive"))
      (node (ref "D1") (pin "A") (pinfunction "A_A") (pintype "passive"))
      (node (ref "R1") (pin "2") (pinfunction "2_2") (pintype "passive"))
      (node (ref "R10") (pin "1") (pinfunction "1_1") (pintype "passive"))
      (node (ref "R2") (pin "1") (pinfunction "1_1") (pintype "passive"))
    )
    (net (code "34") (name "Net-(C6-Pad1)") (class "Default")
      (node (ref "C6") (pin "1") (pinfunction "1_1") (pintype "passive"))
      (node (ref "R6") (pin "1") (pinfunction "1_1") (pintype "passive"))
      (node (ref "R7") (pin "2") (pinfunction "2_2") (pintype "passive"))
    )
    (net (code "35") (name "Net-(D2-PadA)") (class "Default")
      (node (ref "D2") (pin "A") (pinfunction "A_A") (pintype "passive"))
      (node (ref "R5") (pin "1") (pinfunction "1_1") (pintype "passive"))
    )
    (net (code "36") (name "Net-(D3-PadA)") (class "Default")
      (node (ref "D3") (pin "A") (pinfunction "A_A") (pintype "passive"))
      (node (ref "R26") (pin "1") (pinfunction "1_1") (pintype "passive"))
    )
    (net (code "37") (name "Net-(D4-PadA)") (class "Default")
      (node (ref "D4") (pin "A") (pinfunction "A_A") (pintype "passive"))
      (node (ref "R17") (pin "1") (pinfunction "1_1") (pintype "passive"))
    )
    (net (code "38") (name "Net-(D5-PadA)") (class "Default")
      (node (ref "D5") (pin "A") (pinfunction "A_A") (pintype "passive"))
      (node (ref "R27") (pin "1") (pinfunction "1_1") (pintype "passive"))
    )
    (net (code "39") (name "Net-(Q2-D)") (class "Default")
      (node (ref "Q2") (pin "3") (pinfunction "D_3") (pintype "bidirectional"))
      (node (ref "R24") (pin "1") (pinfunction "1_1") (pintype "passive"))
    )
    (net (code "40") (name "Net-(Q4-D)") (class "Default")
      (node (ref "D2") (pin "C") (pinfunction "C_C") (pintype "passive"))
      (node (ref "Q4") (pin "3") (pinfunction "D_3") (pintype "bidirectional"))
    )
    (net (code "41") (name "Net-(Q5-D)") (class "Default")
      (node (ref "Q5") (pin "3") (pinfunction "D_3") (pintype "bidirectional"))
      (node (ref "R17") (pin "2") (pinfunction "2_2") (pintype "passive"))
    )
    (net (code "42") (name "Net-(R20-Pad2)") (class "Default")
      (node (ref "R20") (pin "2") (pinfunction "2_2") (pintype "passive"))
      (node (ref "U$5") (pin "ADR") (pinfunction "ADR_ADR") (pintype "input"))
    )
    (net (code "43") (name "Net-(U$7-VCAP)") (class "Default")
      (node (ref "C14") (pin "1") (pinfunction "1_1") (pintype "passive"))
      (node (ref "U$7") (pin "13") (pinfunction "VCAP_13") (pintype "bidirectional"))
    )
    (net (code "44") (name "OCD") (class "Default")
      (node (ref "R23") (pin "1") (pinfunction "1_1") (pintype "passive"))
      (node (ref "R24") (pin "2") (pinfunction "2_2") (pintype "passive"))
      (node (ref "U$7") (pin "16") (pinfunction "VOC_16") (pintype "bidirectional"))
    )
    (net (code "45") (name "OSC1") (class "Default")
      (node (ref "R19") (pin "2") (pinfunction "2_2") (pintype "passive"))
      (node (ref "U$1") (pin "8") (pinfunction "OSC1_8") (pintype "bidirectional"))
    )
    (net (code "46") (name "OSC2") (class "Default")
      (node (ref "R11") (pin "2") (pinfunction "2_2") (pintype "passive"))
      (node (ref "U$1") (pin "7") (pinfunction "OSC2_7") (pintype "bidirectional"))
    )
    (net (code "47") (name "PI_POWER") (class "Default")
      (node (ref "C7") (pin "+") (pinfunction "+_+") (pintype "passive"))
      (node (ref "R18") (pin "1") (pinfunction "1_1") (pintype "passive"))
      (node (ref "R21") (pin "1") (pinfunction "1_1") (pintype "passive"))
      (node (ref "U$8") (pin "2") (pinfunction "5V_2") (pintype "bidirectional"))
      (node (ref "U$8") (pin "4") (pinfunction "5V_4") (pintype "bidirectional"))
    )
    (net (code "48") (name "PWM") (class "Default")
      (node (ref "J9") (pin "3") (pinfunction "3_3") (pintype "passive"))
      (node (ref "U$8") (pin "33") (pinfunction "GPIO13_33") (pintype "bidirectional"))
    )
    (net (code "49") (name "RESET") (class "Default")
      (node (ref "R1") (pin "1") (pinfunction "1_1") (pintype "passive"))
      (node (ref "U$1") (pin "17") (pinfunction "RESET_17") (pintype "bidirectional"))
    )
    (net (code "50") (name "RX") (class "Default")
      (node (ref "J8") (pin "2") (pinfunction "2_2") (pintype "passive"))
      (node (ref "U$8") (pin "10") (pinfunction "GPIO15_10") (pintype "bidirectional"))
    )
    (net (code "51") (name "RX0_INT") (class "Default")
      (node (ref "U$1") (pin "11") (pinfunction "RX0BF_11") (pintype "bidirectional"))
      (node (ref "U$8") (pin "35") (pinfunction "GPIO19_35") (pintype "bidirectional"))
    )
    (net (code "52") (name "RX1_INT") (class "Default")
      (node (ref "U$1") (pin "10") (pinfunction "RX1BF_10") (pintype "bidirectional"))
      (node (ref "U$8") (pin "29") (pinfunction "GPIO5_29") (pintype "bidirectional"))
    )
    (net (code "53") (name "RXCAN") (class "Default")
      (node (ref "U$1") (pin "2") (pinfunction "RXCAN_2") (pintype "bidirectional"))
      (node (ref "U$2") (pin "4") (pinfunction "RXD_4") (pintype "bidirectional"))
    )
    (net (code "54") (name "SCL") (class "Default")
      (node (ref "J1") (pin "2") (pinfunction "2_2") (pintype "passive"))
      (node (ref "J13") (pin "2") (pinfunction "2_2") (pintype "passive"))
      (node (ref "J14") (pin "2") (pinfunction "2_2") (pintype "passive"))
      (node (ref "J15") (pin "2") (pinfunction "2_2") (pintype "passive"))
      (node (ref "J3") (pin "2") (pinfunction "2_2") (pintype "passive"))
      (node (ref "Q1") (pin "2") (pinfunction "S_2") (pintype "bidirectional"))
      (node (ref "R15") (pin "1") (pinfunction "1_1") (pintype "passive"))
      (node (ref "R9") (pin "2") (pinfunction "2_2") (pintype "passive"))
      (node (ref "U$4") (pin "SCL") (pinfunction "SCL_SCL") (pintype "bidirectional"))
      (node (ref "U$5") (pin "SCL") (pinfunction "SCL_SCL") (pintype "bidirectional"))
      (node (ref "U$8") (pin "5") (pinfunction "GPIO3_5") (pintype "bidirectional"))
    )
    (net (code "55") (name "SCL_ADC") (class "Default")
      (node (ref "Q1") (pin "3") (pinfunction "D_3") (pintype "bidirectional"))
      (node (ref "R14") (pin "2") (pinfunction "2_2") (pintype "passive"))
      (node (ref "U1") (pin "5") (pinfunction "SCL_5") (pintype "bidirectional"))
    )
    (net (code "56") (name "SDA") (class "Default")
      (node (ref "J1") (pin "3") (pinfunction "3_3") (pintype "passive"))
      (node (ref "J13") (pin "3") (pinfunction "3_3") (pintype "passive"))
      (node (ref "J14") (pin "3") (pinfunction "3_3") (pintype "passive"))
      (node (ref "J15") (pin "3") (pinfunction "3_3") (pintype "passive"))
      (node (ref "J3") (pin "3") (pinfunction "3_3") (pintype "passive"))
      (node (ref "Q3") (pin "2") (pinfunction "S_2") (pintype "bidirectional"))
      (node (ref "R12") (pin "1") (pinfunction "1_1") (pintype "passive"))
      (node (ref "R8") (pin "2") (pinfunction "2_2") (pintype "passive"))
      (node (ref "U$4") (pin "SDA") (pinfunction "SDA_SDA") (pintype "bidirectional"))
      (node (ref "U$5") (pin "SDA") (pinfunction "SDA_SDA") (pintype "bidirectional"))
      (node (ref "U$8") (pin "3") (pinfunction "GPIO2_3") (pintype "bidirectional"))
    )
    (net (code "57") (name "SDA_ADC") (class "Default")
      (node (ref "Q3") (pin "3") (pinfunction "D_3") (pintype "bidirectional"))
      (node (ref "R13") (pin "2") (pinfunction "2_2") (pintype "passive"))
      (node (ref "U1") (pin "6") (pinfunction "SDA_6") (pintype "bidirectional"))
    )
    (net (code "58") (name "SOL1_1") (class "Default")
      (node (ref "U$9") (pin "1") (pinfunction "14_1") (pintype "passive"))
      (node (ref "U3") (pin "16") (pinfunction "OUT1_16") (pintype "bidirectional"))
    )
    (net (code "59") (name "SOL2_1") (class "Default")
      (node (ref "U$9") (pin "3") (pinfunction "16_3") (pintype "passive"))
      (node (ref "U3") (pin "15") (pinfunction "OUT2_15") (pintype "bidirectional"))
    )
    (net (code "60") (name "SOL3_1") (class "Default")
      (node (ref "U$9") (pin "5") (pinfunction "18_5") (pintype "passive"))
      (node (ref "U3") (pin "14") (pinfunction "OUT3_14") (pintype "bidirectional"))
    )
    (net (code "61") (name "SOL4_1") (class "Default")
      (node (ref "U$9") (pin "7") (pinfunction "20_7") (pintype "passive"))
      (node (ref "U3") (pin "13") (pinfunction "OUT4_13") (pintype "bidirectional"))
    )
    (net (code "62") (name "SOL5_1") (class "Default")
      (node (ref "U$9") (pin "9") (pinfunction "22_9") (pintype "passive"))
      (node (ref "U3") (pin "12") (pinfunction "OUT5_12") (pintype "bidirectional"))
    )
    (net (code "63") (name "SOL6_1") (class "Default")
      (node (ref "U$9") (pin "11") (pinfunction "24_11") (pintype "passive"))
      (node (ref "U3") (pin "11") (pinfunction "OUT6_11") (pintype "bidirectional"))
    )
    (net (code "64") (name "TX") (class "Default")
      (node (ref "J8") (pin "3") (pinfunction "3_3") (pintype "passive"))
      (node (ref "U$8") (pin "8") (pinfunction "GPIO14_8") (pintype "bidirectional"))
    )
    (net (code "65") (name "TXCAN") (class "Default")
      (node (ref "U$1") (pin "1") (pinfunction "TXCAN_1") (pintype "bidirectional"))
      (node (ref "U$2") (pin "1") (pinfunction "TXD_1") (pintype "bidirectional"))
    )
    (net (code "66") (name "unconnected-(J10-Pad1)") (class "Default")
      (node (ref "J10") (pin "1") (pinfunction "1_1") (pintype "bidirectional"))
    )
    (net (code "67") (name "unconnected-(J10-Pad4)") (class "Default")
      (node (ref "J10") (pin "4") (pinfunction "4_4") (pintype "bidirectional"))
    )
    (net (code "68") (name "unconnected-(J11-Pad1)") (class "Default")
      (node (ref "J11") (pin "1") (pinfunction "1_1") (pintype "bidirectional"))
    )
    (net (code "69") (name "unconnected-(J11-Pad4)") (class "Default")
      (node (ref "J11") (pin "4") (pinfunction "4_4") (pintype "bidirectional"))
    )
    (net (code "70") (name "unconnected-(U$1-CLKOUT{slash}SOF-Pad3)") (class "Default")
      (node (ref "U$1") (pin "3") (pinfunction "CLKOUT/SOF_3") (pintype "bidirectional"))
    )
    (net (code "71") (name "unconnected-(U$1-TX0RTS-Pad4)") (class "Default")
      (node (ref "U$1") (pin "4") (pinfunction "TX0RTS_4") (pintype "bidirectional"))
    )
    (net (code "72") (name "unconnected-(U$1-TX1RTS-Pad5)") (class "Default")
      (node (ref "U$1") (pin "5") (pinfunction "TX1RTS_5") (pintype "bidirectional"))
    )
    (net (code "73") (name "unconnected-(U$1-TX2RTS-Pad6)") (class "Default")
      (node (ref "U$1") (pin "6") (pinfunction "TX2RTS_6") (pintype "bidirectional"))
    )
    (net (code "74") (name "unconnected-(U$4-PadAI2)") (class "Default")
      (node (ref "U$4") (pin "AI2") (pinfunction "AI2_AI2") (pintype "output"))
    )
    (net (code "75") (name "unconnected-(U$4-PadGI2)") (class "Default")
      (node (ref "U$4") (pin "GI2") (pinfunction "GI2_GI2") (pintype "output"))
    )
    (net (code "76") (name "unconnected-(U$5-PadPS0)") (class "Default")
      (node (ref "U$5") (pin "PS0") (pinfunction "PS0_PS0") (pintype "input"))
    )
    (net (code "77") (name "unconnected-(U$5-PadPS1)") (class "Default")
      (node (ref "U$5") (pin "PS1") (pinfunction "PS1_PS1") (pintype "input"))
    )
    (net (code "78") (name "unconnected-(U$8-3V3-Pad1)") (class "Default")
      (node (ref "U$8") (pin "1") (pinfunction "3V3_1") (pintype "bidirectional"))
    )
    (net (code "79") (name "unconnected-(U$8-3V3-Pad17)") (class "Default")
      (node (ref "U$8") (pin "17") (pinfunction "3V3_17") (pintype "bidirectional"))
    )
    (net (code "80") (name "unconnected-(U$8-GPIO6-Pad31)") (class "Default")
      (node (ref "U$8") (pin "31") (pinfunction "GPIO6_31") (pintype "bidirectional"))
    )
    (net (code "81") (name "unconnected-(U$8-ID_SC*-Pad28)") (class "Default")
      (node (ref "U$8") (pin "28") (pinfunction "ID_SC*_28") (pintype "bidirectional"))
    )
    (net (code "82") (name "unconnected-(U$8-ID_SD*-Pad27)") (class "Default")
      (node (ref "U$8") (pin "27") (pinfunction "ID_SD*_27") (pintype "bidirectional"))
    )
    (net (code "83") (name "unconnected-(U1-AIN0-Pad1)") (class "Default")
      (node (ref "U1") (pin "1") (pinfunction "AIN0_1") (pintype "bidirectional"))
    )
    (net (code "84") (name "unconnected-(U3-IN7-Pad7)") (class "Default")
      (node (ref "U3") (pin "7") (pinfunction "IN7_7") (pintype "bidirectional"))
    )
    (net (code "85") (name "unconnected-(U3-OUT7-Pad10)") (class "Default")
      (node (ref "U3") (pin "10") (pinfunction "OUT7_10") (pintype "bidirectional"))
    )
    (net (code "86") (name "~{AMP_FAULT}") (class "Default")
      (node (ref "Q5") (pin "1") (pinfunction "G_1") (pintype "bidirectional"))
      (node (ref "R16") (pin "1") (pinfunction "1_1") (pintype "passive"))
      (node (ref "U$7") (pin "9") (pinfunction "~{FAULTB}_9") (pintype "bidirectional"))
    )
    (net (code "87") (name "~{AMP_RESET}") (class "Default")
      (node (ref "Q2") (pin "1") (pinfunction "G_1") (pintype "bidirectional"))
      (node (ref "R25") (pin "2") (pinfunction "2_2") (pintype "passive"))
      (node (ref "U$6") (pin "1") (pinfunction "P$1_1") (pintype "bidirectional"))
      (node (ref "U$8") (pin "7") (pinfunction "GPIO4_7") (pintype "bidirectional"))
    )
  )
)
